# AFF.net
KiCad netlist of a schematic drawn in Altium Designer
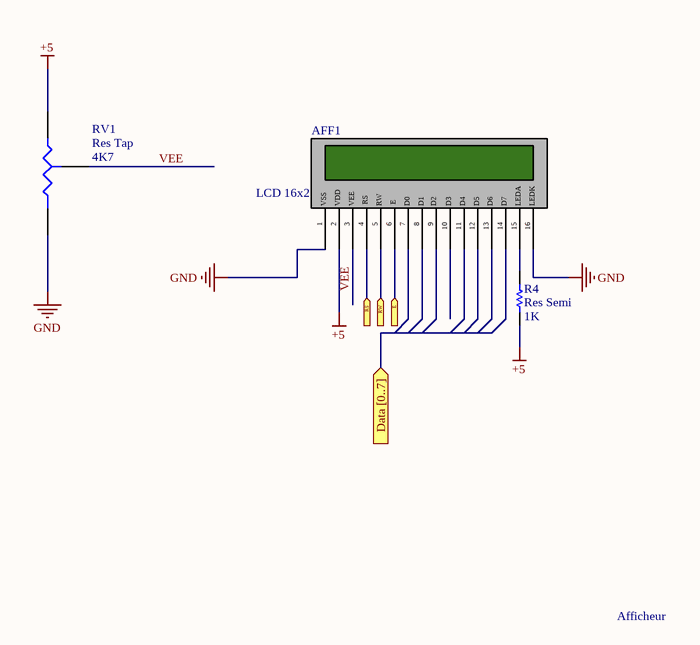
[diagram p0: AFF.SchDoc]

(export (version "E")
  (design (tool "Eeschema 10.0.6"))
  (components
    (comp (ref "AFF1") (value "LCD 16x2") (libsource (lib "TP3") (part "LCD 16x2")))
    (comp (ref "R4")
      (value "Res Semi")
      (footprint "AXIAL-0.5")
      (description "Semiconductor Resistor")
      (fields (field (name "ALTIUM_VALUE") "1K") (field (name "PUBLISHER") "Altium Limited"))
      (libsource (lib "Miscellaneous Devices") (part "Res Semi"))
    )
    (comp (ref "RV1")
      (value "Res Tap")
      (footprint "VR3")
      (description "Tapped Resistor")
      (fields (field (name "ALTIUM_VALUE") "4K7") (field (name "PUBLISHER") "Altium Limited"))
      (libsource (lib "Miscellaneous Devices") (part "Res Tap"))
    )
  )
  (nets
    (net (code "1") (name "+5") (class "Default")
      (node (ref "AFF1") (pin "2") (pintype "passive"))
      (node (ref "R4") (pin "1") (pinfunction "1_1") (pintype "passive"))
      (node (ref "RV1") (pin "1") (pinfunction "A_1") (pintype "passive"))
    )
    (net (code "3") (name "/E") (class "Default") (node (ref "AFF1") (pin "6") (pintype "passive")))
    (net (code "4") (name "/RS") (class "Default") (node (ref "AFF1") (pin "4") (pintype "passive")))
    (net (code "5") (name "/RW") (class "Default") (node (ref "AFF1") (pin "5") (pintype "passive")))
    (net (code "6") (name "/VEE") (class "Default")
      (node (ref "AFF1") (pin "3") (pintype "passive"))
      (node (ref "RV1") (pin "3") (pinfunction "TAP_3") (pintype "passive"))
    )
    (net (code "7") (name "GND") (class "Default")
      (node (ref "AFF1") (pin "1") (pintype "passive"))
      (node (ref "AFF1") (pin "16") (pintype "passive"))
      (node (ref "RV1") (pin "2") (pinfunction "B_2") (pintype "passive"))
    )
    (net (code "8") (name "Net-(AFF1-Pad15)") (class "Default")
      (node (ref "AFF1") (pin "15") (pintype "passive"))
      (node (ref "R4") (pin "2") (pinfunction "2_2") (pintype "passive"))
    )
    (net (code "9") (name "unconnected-(AFF1-Pad7)") (class "Default")
      (node (ref "AFF1") (pin "7") (pintype "passive"))
    )
    (net (code "10") (name "unconnected-(AFF1-Pad8)") (class "Default")
      (node (ref "AFF1") (pin "8") (pintype "passive"))
    )
    (net (code "11") (name "unconnected-(AFF1-Pad9)") (class "Default")
      (node (ref "AFF1") (pin "9") (pintype "passive"))
    )
    (net (code "12") (name "unconnected-(AFF1-Pad10)") (class "Default")
      (node (ref "AFF1") (pin "10") (pintype "passive"))
    )
    (net (code "13") (name "unconnected-(AFF1-Pad11)") (class "Default")
      (node (ref "AFF1") (pin "11") (pintype "passive"))
    )
    (net (code "14") (name "unconnected-(AFF1-Pad12)") (class "Default")
      (node (ref "AFF1") (pin "12") (pintype "passive"))
    )
    (net (code "15") (name "unconnected-(AFF1-Pad13)") (class "Default")
      (node (ref "AFF1") (pin "13") (pintype "passive"))
    )
    (net (code "16") (name "unconnected-(AFF1-Pad14)") (class "Default")
      (node (ref "AFF1") (pin "14") (pintype "passive"))
    )
  )
)
